# Microcontroller.net
KiCad netlist of a schematic drawn in Altium Designer
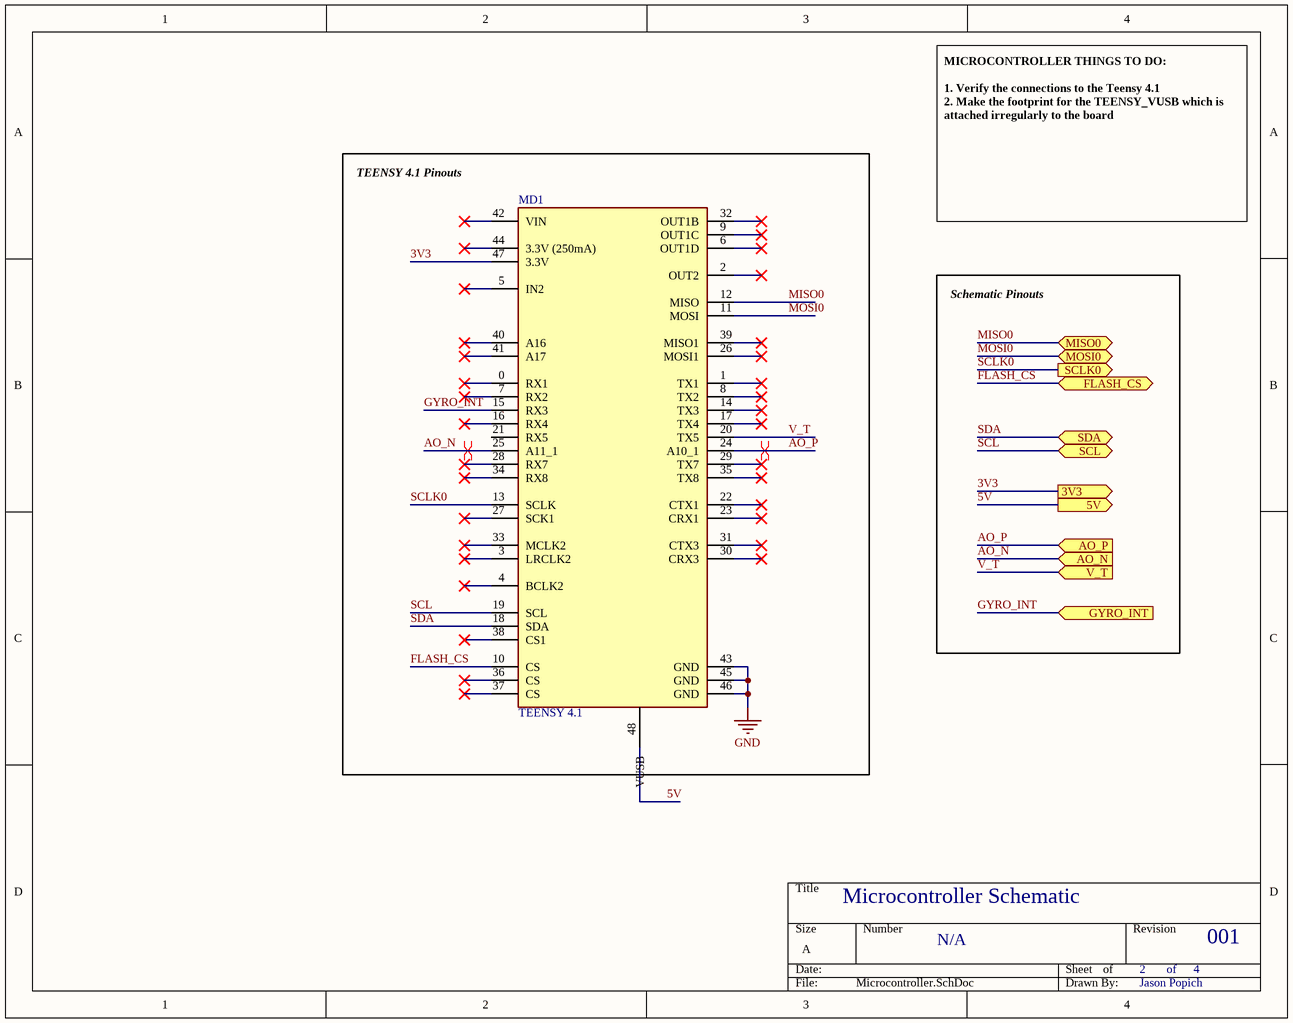
[diagram p0: Microcontroller.SchDoc]

(export (version "E")
  (design (tool "Eeschema 10.0.6"))
  (components
    (comp (ref "MD1")
      (value "TEENSY 4.1")
      (footprint "Teensy4_1")
      (description "TEENSY 4.1 (HEADERS)")
      (libsource (lib "GAINS_SCH") (part "080115a1ce54750370cf87ec145ee29"))
    )
  )
  (nets
    (net (code "1") (name "/3V3") (class "Default")
      (node (ref "MD1") (pin "47") (pinfunction "3.3V_47") (pintype "passive"))
    )
    (net (code "3") (name "/AO_N") (class "Default")
      (node (ref "MD1") (pin "25") (pinfunction "A11_1_25") (pintype "passive"))
    )
    (net (code "4") (name "/AO_P") (class "Default")
      (node (ref "MD1") (pin "24") (pinfunction "A10_1_24") (pintype "passive"))
    )
    (net (code "5") (name "/FLASH_CS") (class "Default")
      (node (ref "MD1") (pin "10") (pinfunction "CS_10") (pintype "passive"))
    )
    (net (code "6") (name "/GYRO_INT") (class "Default")
      (node (ref "MD1") (pin "15") (pinfunction "RX3_15") (pintype "passive"))
    )
    (net (code "7") (name "/MISO0") (class "Default")
      (node (ref "MD1") (pin "12") (pinfunction "MISO_12") (pintype "passive"))
    )
    (net (code "8") (name "/MOSI0") (class "Default")
      (node (ref "MD1") (pin "11") (pinfunction "MOSI_11") (pintype "passive"))
    )
    (net (code "9") (name "/SCL") (class "Default")
      (node (ref "MD1") (pin "19") (pinfunction "SCL_19") (pintype "passive"))
    )
    (net (code "10") (name "/SCLK0") (class "Default")
      (node (ref "MD1") (pin "13") (pinfunction "SCLK_13") (pintype "passive"))
    )
    (net (code "11") (name "/SDA") (class "Default")
      (node (ref "MD1") (pin "18") (pinfunction "SDA_18") (pintype "passive"))
    )
    (net (code "12") (name "/V_T") (class "Default")
      (node (ref "MD1") (pin "20") (pinfunction "TX5_20") (pintype "passive"))
    )
    (net (code "13") (name "GND") (class "Default")
      (node (ref "MD1") (pin "43") (pinfunction "GND_43") (pintype "passive"))
      (node (ref "MD1") (pin "45") (pinfunction "GND_45") (pintype "passive"))
      (node (ref "MD1") (pin "46") (pinfunction "GND_46") (pintype "passive"))
    )
    (net (code "14") (name "unconnected-(MD1-3.3V_(250mA)-Pad44)") (class "Default")
      (node (ref "MD1") (pin "44") (pinfunction "3.3V_(250mA)_44") (pintype "passive+no_connect"))
    )
    (net (code "15") (name "unconnected-(MD1-A16-Pad40)") (class "Default")
      (node (ref "MD1") (pin "40") (pinfunction "A16_40") (pintype "passive+no_connect"))
    )
    (net (code "16") (name "unconnected-(MD1-A17-Pad41)") (class "Default")
      (node (ref "MD1") (pin "41") (pinfunction "A17_41") (pintype "passive+no_connect"))
    )
    (net (code "17") (name "unconnected-(MD1-BCLK2-Pad4)") (class "Default")
      (node (ref "MD1") (pin "4") (pinfunction "BCLK2_4") (pintype "passive+no_connect"))
    )
    (net (code "18") (name "unconnected-(MD1-CRX1-Pad23)") (class "Default")
      (node (ref "MD1") (pin "23") (pinfunction "CRX1_23") (pintype "passive+no_connect"))
    )
    (net (code "19") (name "unconnected-(MD1-CRX3-Pad30)") (class "Default")
      (node (ref "MD1") (pin "30") (pinfunction "CRX3_30") (pintype "passive+no_connect"))
    )
    (net (code "20") (name "unconnected-(MD1-CS-Pad36)") (class "Default")
      (node (ref "MD1") (pin "36") (pinfunction "CS_36") (pintype "passive+no_connect"))
    )
    (net (code "21") (name "unconnected-(MD1-CS-Pad37)") (class "Default")
      (node (ref "MD1") (pin "37") (pinfunction "CS_37") (pintype "passive+no_connect"))
    )
    (net (code "22") (name "unconnected-(MD1-CS1-Pad38)") (class "Default")
      (node (ref "MD1") (pin "38") (pinfunction "CS1_38") (pintype "passive+no_connect"))
    )
    (net (code "23") (name "unconnected-(MD1-CTX1-Pad22)") (class "Default")
      (node (ref "MD1") (pin "22") (pinfunction "CTX1_22") (pintype "passive+no_connect"))
    )
    (net (code "24") (name "unconnected-(MD1-CTX3-Pad31)") (class "Default")
      (node (ref "MD1") (pin "31") (pinfunction "CTX3_31") (pintype "passive+no_connect"))
    )
    (net (code "25") (name "unconnected-(MD1-IN2-Pad5)") (class "Default")
      (node (ref "MD1") (pin "5") (pinfunction "IN2_5") (pintype "passive+no_connect"))
    )
    (net (code "26") (name "unconnected-(MD1-LRCLK2-Pad3)") (class "Default")
      (node (ref "MD1") (pin "3") (pinfunction "LRCLK2_3") (pintype "passive+no_connect"))
    )
    (net (code "27") (name "unconnected-(MD1-MCLK2-Pad33)") (class "Default")
      (node (ref "MD1") (pin "33") (pinfunction "MCLK2_33") (pintype "passive+no_connect"))
    )
    (net (code "28") (name "unconnected-(MD1-MISO1-Pad39)") (class "Default")
      (node (ref "MD1") (pin "39") (pinfunction "MISO1_39") (pintype "passive+no_connect"))
    )
    (net (code "29") (name "unconnected-(MD1-MOSI1-Pad26)") (class "Default")
      (node (ref "MD1") (pin "26") (pinfunction "MOSI1_26") (pintype "passive+no_connect"))
    )
    (net (code "30") (name "unconnected-(MD1-OUT1B-Pad32)") (class "Default")
      (node (ref "MD1") (pin "32") (pinfunction "OUT1B_32") (pintype "passive+no_connect"))
    )
    (net (code "31") (name "unconnected-(MD1-OUT1C-Pad9)") (class "Default")
      (node (ref "MD1") (pin "9") (pinfunction "OUT1C_9") (pintype "passive+no_connect"))
    )
    (net (code "32") (name "unconnected-(MD1-OUT1D-Pad6)") (class "Default")
      (node (ref "MD1") (pin "6") (pinfunction "OUT1D_6") (pintype "passive+no_connect"))
    )
    (net (code "33") (name "unconnected-(MD1-OUT2-Pad2)") (class "Default")
      (node (ref "MD1") (pin "2") (pinfunction "OUT2_2") (pintype "passive+no_connect"))
    )
    (net (code "34") (name "unconnected-(MD1-RX1-Pad0)") (class "Default")
      (node (ref "MD1") (pin "0") (pinfunction "RX1_0") (pintype "passive+no_connect"))
    )
    (net (code "35") (name "unconnected-(MD1-RX2-Pad7)") (class "Default")
      (node (ref "MD1") (pin "7") (pinfunction "RX2_7") (pintype "passive+no_connect"))
    )
    (net (code "36") (name "unconnected-(MD1-RX4-Pad16)") (class "Default")
      (node (ref "MD1") (pin "16") (pinfunction "RX4_16") (pintype "passive+no_connect"))
    )
    (net (code "37") (name "unconnected-(MD1-RX5-Pad21)") (class "Default")
      (node (ref "MD1") (pin "21") (pinfunction "RX5_21") (pintype "passive"))
    )
    (net (code "38") (name "unconnected-(MD1-RX7-Pad28)") (class "Default")
      (node (ref "MD1") (pin "28") (pinfunction "RX7_28") (pintype "passive+no_connect"))
    )
    (net (code "39") (name "unconnected-(MD1-RX8-Pad34)") (class "Default")
      (node (ref "MD1") (pin "34") (pinfunction "RX8_34") (pintype "passive+no_connect"))
    )
    (net (code "40") (name "unconnected-(MD1-SCK1-Pad27)") (class "Default")
      (node (ref "MD1") (pin "27") (pinfunction "SCK1_27") (pintype "passive+no_connect"))
    )
    (net (code "41") (name "unconnected-(MD1-TX1-Pad1)") (class "Default")
      (node (ref "MD1") (pin "1") (pinfunction "TX1_1") (pintype "passive+no_connect"))
    )
    (net (code "42") (name "unconnected-(MD1-TX2-Pad8)") (class "Default")
      (node (ref "MD1") (pin "8") (pinfunction "TX2_8") (pintype "passive+no_connect"))
    )
    (net (code "43") (name "unconnected-(MD1-TX3-Pad14)") (class "Default")
      (node (ref "MD1") (pin "14") (pinfunction "TX3_14") (pintype "passive+no_connect"))
    )
    (net (code "44") (name "unconnected-(MD1-TX4-Pad17)") (class "Default")
      (node (ref "MD1") (pin "17") (pinfunction "TX4_17") (pintype "passive+no_connect"))
    )
    (net (code "45") (name "unconnected-(MD1-TX7-Pad29)") (class "Default")
      (node (ref "MD1") (pin "29") (pinfunction "TX7_29") (pintype "passive+no_connect"))
    )
    (net (code "46") (name "unconnected-(MD1-TX8-Pad35)") (class "Default")
      (node (ref "MD1") (pin "35") (pinfunction "TX8_35") (pintype "passive+no_connect"))
    )
    (net (code "47") (name "unconnected-(MD1-VIN-Pad42)") (class "Default")
      (node (ref "MD1") (pin "42") (pinfunction "VIN_42") (pintype "passive+no_connect"))
    )
    (net (code "48") (name "unconnected-(MD1-VUSB-Pad48)") (class "Default")
      (node (ref "MD1") (pin "48") (pinfunction "VUSB_48") (pintype "passive"))
    )
  )
)
